# mainboard_rs485_v1_0.net
KiCad netlist of a schematic drawn in Altium Designer
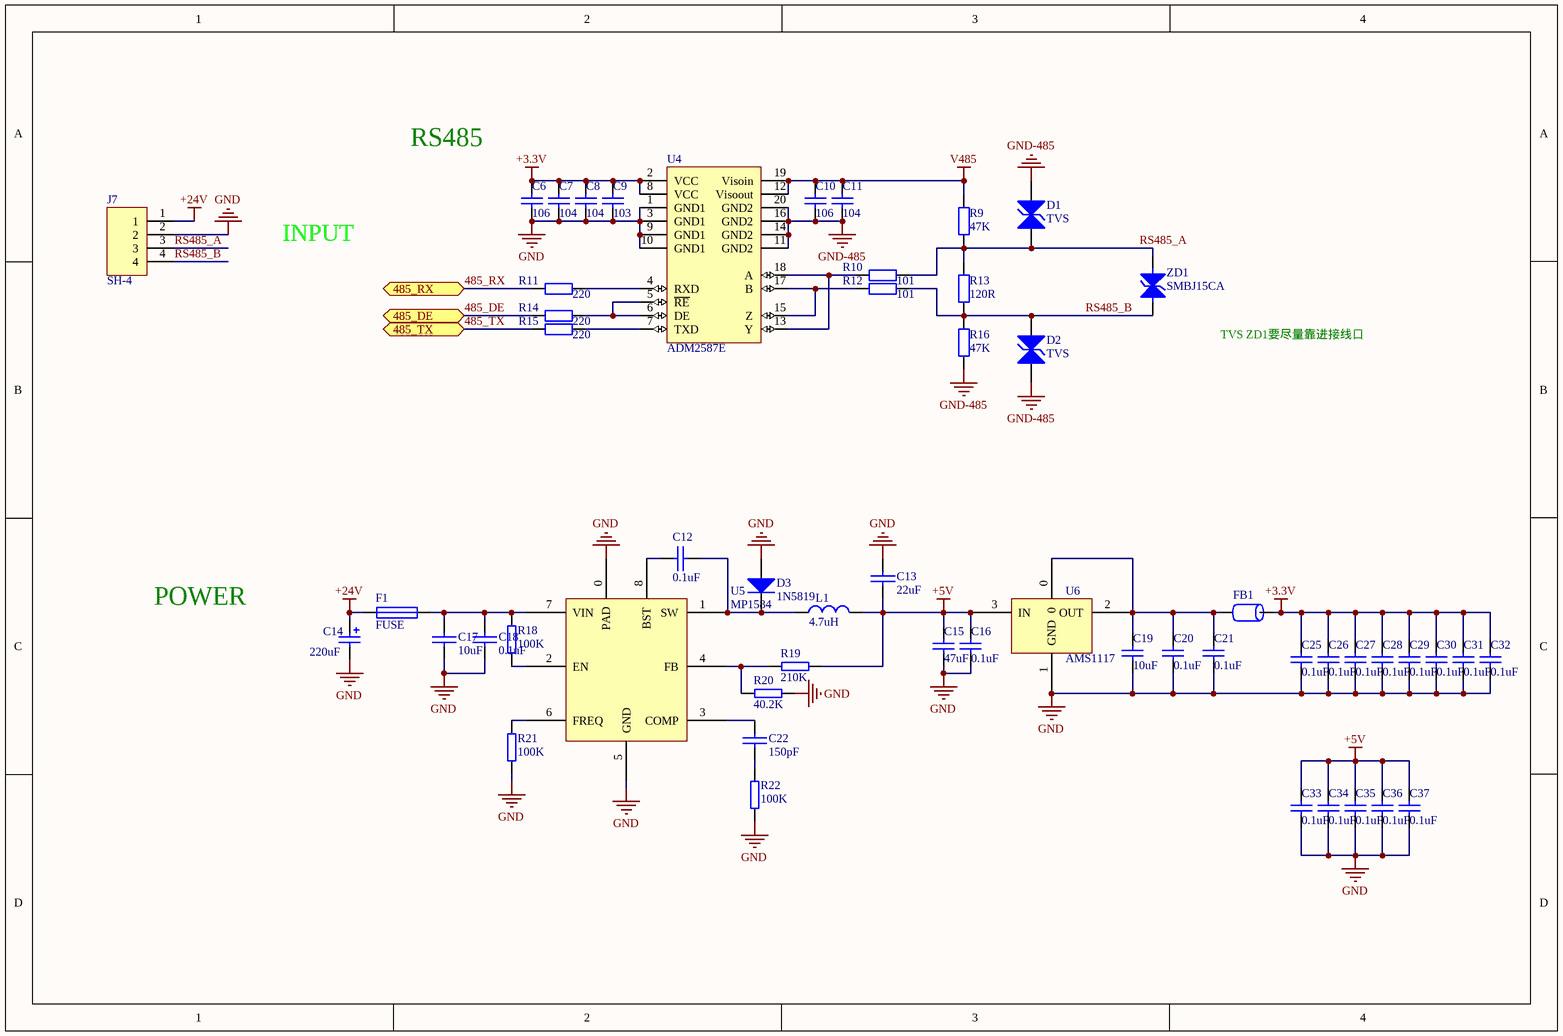
[diagram p0: mainboard_rs485.v1.0.SchDoc]

(export (version "E")
  (design (tool "Eeschema 10.0.6"))
  (components
    (comp (ref "C6")
      (value "106")
      (footprint "0805")
      (description "Capacitor")
      (fields (field (name "PUBLISHER") "Altium Limited"))
      (libsource (lib "TIAN's Schlib") (part "Cap"))
    )
    (comp (ref "C7")
      (value "104")
      (footprint "0805")
      (description "Capacitor")
      (fields (field (name "PUBLISHER") "Altium Limited"))
      (libsource (lib "TIAN's Schlib") (part "Cap"))
    )
    (comp (ref "C8")
      (value "104")
      (footprint "0805")
      (description "Capacitor")
      (fields (field (name "PUBLISHER") "Altium Limited"))
      (libsource (lib "TIAN's Schlib") (part "Cap"))
    )
    (comp (ref "C9")
      (value "103")
      (footprint "0805")
      (description "Capacitor")
      (fields (field (name "PUBLISHER") "Altium Limited"))
      (libsource (lib "TIAN's Schlib") (part "Cap"))
    )
    (comp (ref "C10")
      (value "106")
      (footprint "0805")
      (description "Capacitor")
      (fields (field (name "PUBLISHER") "Altium Limited"))
      (libsource (lib "TIAN's Schlib") (part "Cap"))
    )
    (comp (ref "C11")
      (value "104")
      (footprint "0805")
      (description "Capacitor")
      (fields (field (name "PUBLISHER") "Altium Limited"))
      (libsource (lib "TIAN's Schlib") (part "Cap"))
    )
    (comp (ref "C12")
      (value "0.1uF")
      (footprint "0805")
      (description "电容")
      (libsource (lib "Component") (part "CAP"))
    )
    (comp (ref "C13")
      (value "22uF")
      (footprint "0805")
      (description "电容")
      (libsource (lib "Component") (part "CAP"))
    )
    (comp (ref "C14")
      (value "220uF")
      (footprint "CAP-5mm")
      (description "电解电容")
      (libsource (lib "Component") (part "Cap Pol1"))
    )
    (comp (ref "C15") (value "47uF") (footprint "1812") (libsource (lib "Componet") (part "Cap0805")))
    (comp (ref "C16") (value "0.1uF") (footprint "0805") (libsource (lib "Componet") (part "Cap0805")))
    (comp (ref "C17")
      (value "10uF")
      (footprint "0805")
      (description "电容")
      (libsource (lib "Component") (part "CAP"))
    )
    (comp (ref "C18")
      (value "0.1uF")
      (footprint "0805")
      (description "电容")
      (libsource (lib "Component") (part "CAP"))
    )
    (comp (ref "C19") (value "10uF") (footprint "0805") (libsource (lib "Componet") (part "Cap0805")))
    (comp (ref "C20") (value "0.1uF") (footprint "0805") (libsource (lib "Componet") (part "Cap0805")))
    (comp (ref "C21") (value "0.1uF") (footprint "0805") (libsource (lib "Componet") (part "Cap0805")))
    (comp (ref "C22")
      (value "150pF")
      (footprint "0805")
      (description "电容")
      (libsource (lib "Component") (part "CAP"))
    )
    (comp (ref "C25") (value "0.1uF") (footprint "0805") (libsource (lib "Componet") (part "Cap0805")))
    (comp (ref "C26") (value "0.1uF") (footprint "0805") (libsource (lib "Componet") (part "Cap0805")))
    (comp (ref "C27") (value "0.1uF") (footprint "0805") (libsource (lib "Componet") (part "Cap0805")))
    (comp (ref "C28") (value "0.1uF") (footprint "0805") (libsource (lib "Componet") (part "Cap0805")))
    (comp (ref "C29") (value "0.1uF") (footprint "0805") (libsource (lib "Componet") (part "Cap0805")))
    (comp (ref "C30") (value "0.1uF") (footprint "0805") (libsource (lib "Componet") (part "Cap0805")))
    (comp (ref "C31") (value "0.1uF") (footprint "0805") (libsource (lib "Componet") (part "Cap0805")))
    (comp (ref "C32") (value "0.1uF") (footprint "0805") (libsource (lib "Componet") (part "Cap0805")))
    (comp (ref "C33") (value "0.1uF") (footprint "0805") (libsource (lib "Componet") (part "Cap0805")))
    (comp (ref "C34") (value "0.1uF") (footprint "0805") (libsource (lib "Componet") (part "Cap0805")))
    (comp (ref "C35") (value "0.1uF") (footprint "0805") (libsource (lib "Componet") (part "Cap0805")))
    (comp (ref "C36") (value "0.1uF") (footprint "0805") (libsource (lib "Componet") (part "Cap0805")))
    (comp (ref "C37") (value "0.1uF") (footprint "0805") (libsource (lib "Componet") (part "Cap0805")))
    (comp (ref "D1")
      (value "TVS")
      (footprint "SMBJ_DO-214")
      (fields (field (name "PUBLISHER") "Altium Limited"))
      (libsource (lib "TIAN's Schlib") (part "TVS"))
    )
    (comp (ref "D2")
      (value "TVS")
      (footprint "SMBJ_DO-214")
      (fields (field (name "PUBLISHER") "Altium Limited"))
      (libsource (lib "TIAN's Schlib") (part "TVS"))
    )
    (comp (ref "D3")
      (value "1N5819")
      (footprint "Diode_TP2")
      (description "二极管")
      (fields (field (name "PUBLISHER") "Altium Limited"))
      (libsource (lib "Component") (part "Diode"))
    )
    (comp (ref "F1")
      (value "FUSE")
      (footprint "1206")
      (description "保险丝")
      (libsource (lib "Component") (part "FUSE"))
    )
    (comp (ref "FB1") (value "FERRITE") (footprint "0805") (libsource (lib "Connector") (part "FERRITE")))
    (comp (ref "J7") (value "SH-4") (footprint "J5.08_4(NoEar)") (libsource (lib "Connector") (part "SH-4")))
    (comp (ref "L1")
      (value "4.7uH")
      (footprint "Inductance6*6")
      (description "电感")
      (libsource (lib "Component") (part "Inductor"))
    )
    (comp (ref "R9")
      (value "47K")
      (footprint "0805")
      (description "Resistor")
      (fields (field (name "PUBLISHER") "Altium Limited"))
      (libsource (lib "TIAN's Schlib") (part "Res2"))
    )
    (comp (ref "R10")
      (value "101")
      (footprint "0805")
      (description "Resistor")
      (fields (field (name "PUBLISHER") "Altium Limited"))
      (libsource (lib "") (part "Res2_1"))
    )
    (comp (ref "R11")
      (value "220")
      (footprint "0805")
      (description "Resistor")
      (fields (field (name "PUBLISHER") "Altium Limited"))
      (libsource (lib "TIAN's Schlib") (part "Res2"))
    )
    (comp (ref "R12")
      (value "101")
      (footprint "0805")
      (description "Resistor")
      (fields (field (name "PUBLISHER") "Altium Limited"))
      (libsource (lib "") (part "Res2_1"))
    )
    (comp (ref "R13")
      (value "120R")
      (footprint "0805")
      (description "Resistor")
      (fields (field (name "PUBLISHER") "Altium Limited"))
      (libsource (lib "TIAN's Schlib") (part "Res2"))
    )
    (comp (ref "R14")
      (value "220")
      (footprint "0805")
      (description "Resistor")
      (fields (field (name "PUBLISHER") "Altium Limited"))
      (libsource (lib "TIAN's Schlib") (part "Res2"))
    )
    (comp (ref "R15")
      (value "220")
      (footprint "0805")
      (description "Resistor")
      (fields (field (name "PUBLISHER") "Altium Limited"))
      (libsource (lib "TIAN's Schlib") (part "Res2"))
    )
    (comp (ref "R16")
      (value "47K")
      (footprint "0805")
      (description "Resistor")
      (fields (field (name "PUBLISHER") "Altium Limited"))
      (libsource (lib "TIAN's Schlib") (part "Res2"))
    )
    (comp (ref "R18")
      (value "100K")
      (footprint "0805")
      (description "电阻")
      (libsource (lib "Component") (part "RES"))
    )
    (comp (ref "R19")
      (value "210K")
      (footprint "0805")
      (description "电阻")
      (libsource (lib "Component") (part "RES"))
    )
    (comp (ref "R20")
      (value "40.2K")
      (footprint "0805")
      (description "电阻")
      (libsource (lib "Component") (part "RES"))
    )
    (comp (ref "R21")
      (value "100K")
      (footprint "0805")
      (description "电阻")
      (libsource (lib "Component") (part "RES"))
    )
    (comp (ref "R22")
      (value "100K")
      (footprint "0805")
      (description "电阻")
      (libsource (lib "Component") (part "RES"))
    )
    (comp (ref "U4")
      (value "ADM2587E")
      (footprint "SOIC_W_20")
      (description "isolated DC-DC RS485")
      (libsource (lib "TIAN's Schlib") (part "ADM2587E"))
    )
    (comp (ref "U5") (value "MP1584") (footprint "MP1584") (libsource (lib "Chip") (part "MP1584")))
    (comp (ref "U6") (value "AMS1117") (footprint "TO-223") (libsource (lib "Chip") (part "AMS1117")))
    (comp (ref "ZD1")
      (value "SMBJ15CA")
      (footprint "DO-214AA/SMB")
      (description "瞬态抑制二极管")
      (libsource (lib "ALARM") (part "TVS"))
    )
  )
  (nets
    (net (code "1") (name "+3.3V") (class "Default")
      (node (ref "C25") (pin "2") (pinfunction "2_2") (pintype "passive"))
      (node (ref "C26") (pin "2") (pinfunction "2_2") (pintype "passive"))
      (node (ref "C27") (pin "2") (pinfunction "2_2") (pintype "passive"))
      (node (ref "C28") (pin "2") (pinfunction "2_2") (pintype "passive"))
      (node (ref "C29") (pin "2") (pinfunction "2_2") (pintype "passive"))
      (node (ref "C30") (pin "2") (pinfunction "2_2") (pintype "passive"))
      (node (ref "C31") (pin "2") (pinfunction "2_2") (pintype "passive"))
      (node (ref "C32") (pin "2") (pinfunction "2_2") (pintype "passive"))
      (node (ref "C6") (pin "2") (pinfunction "2_2") (pintype "passive"))
      (node (ref "C7") (pin "2") (pinfunction "2_2") (pintype "passive"))
      (node (ref "C8") (pin "2") (pinfunction "2_2") (pintype "passive"))
      (node (ref "C9") (pin "2") (pinfunction "2_2") (pintype "passive"))
      (node (ref "FB1") (pin "2") (pinfunction "2_2") (pintype "passive"))
      (node (ref "U4") (pin "2") (pinfunction "VCC_2") (pintype "passive"))
      (node (ref "U4") (pin "8") (pinfunction "VCC_8") (pintype "passive"))
    )
    (net (code "2") (name "+5V") (class "Default")
      (node (ref "C13") (pin "2") (pinfunction "2_2") (pintype "passive"))
      (node (ref "C15") (pin "2") (pinfunction "2_2") (pintype "passive"))
      (node (ref "C16") (pin "2") (pinfunction "2_2") (pintype "passive"))
      (node (ref "C33") (pin "2") (pinfunction "2_2") (pintype "passive"))
      (node (ref "C34") (pin "2") (pinfunction "2_2") (pintype "passive"))
      (node (ref "C35") (pin "2") (pinfunction "2_2") (pintype "passive"))
      (node (ref "C36") (pin "2") (pinfunction "2_2") (pintype "passive"))
      (node (ref "C37") (pin "2") (pinfunction "2_2") (pintype "passive"))
      (node (ref "L1") (pin "2") (pinfunction "2_2") (pintype "passive"))
      (node (ref "R19") (pin "1") (pinfunction "1_1") (pintype "passive"))
      (node (ref "U6") (pin "3") (pinfunction "IN_3") (pintype "passive"))
    )
    (net (code "3") (name "+24V") (class "Default")
      (node (ref "C14") (pin "1") (pinfunction "1_1") (pintype "passive"))
      (node (ref "F1") (pin "1") (pinfunction "1_1") (pintype "passive"))
      (node (ref "J7") (pin "1") (pinfunction "1_1") (pintype "passive"))
    )
    (net (code "4") (name "/485_DE") (class "Default")
      (node (ref "R14") (pin "1") (pinfunction "1_1") (pintype "passive"))
    )
    (net (code "5") (name "/485_RX") (class "Default")
      (node (ref "R11") (pin "1") (pinfunction "1_1") (pintype "passive"))
    )
    (net (code "6") (name "/485_TX") (class "Default")
      (node (ref "R15") (pin "1") (pinfunction "1_1") (pintype "passive"))
    )
    (net (code "7") (name "/RS485_A") (class "Default")
      (node (ref "D1") (pin "2") (pinfunction "K_2") (pintype "passive"))
      (node (ref "J7") (pin "3") (pinfunction "3_3") (pintype "passive"))
      (node (ref "R10") (pin "2") (pinfunction "2_2") (pintype "passive"))
      (node (ref "R13") (pin "2") (pinfunction "2_2") (pintype "passive"))
      (node (ref "R9") (pin "1") (pinfunction "1_1") (pintype "passive"))
      (node (ref "ZD1") (pin "1") (pinfunction "1_1") (pintype "passive"))
    )
    (net (code "8") (name "/RS485_B") (class "Default")
      (node (ref "D2") (pin "2") (pinfunction "K_2") (pintype "passive"))
      (node (ref "J7") (pin "4") (pinfunction "4_4") (pintype "passive"))
      (node (ref "R12") (pin "2") (pinfunction "2_2") (pintype "passive"))
      (node (ref "R13") (pin "1") (pinfunction "1_1") (pintype "passive"))
      (node (ref "R16") (pin "2") (pinfunction "2_2") (pintype "passive"))
      (node (ref "ZD1") (pin "2") (pinfunction "2_2") (pintype "passive"))
    )
    (net (code "9") (name "GND") (class "Default")
      (node (ref "C13") (pin "1") (pinfunction "1_1") (pintype "passive"))
      (node (ref "C14") (pin "2") (pinfunction "2_2") (pintype "passive"))
      (node (ref "C15") (pin "1") (pinfunction "1_1") (pintype "passive"))
      (node (ref "C16") (pin "1") (pinfunction "1_1") (pintype "passive"))
      (node (ref "C17") (pin "2") (pinfunction "2_2") (pintype "passive"))
      (node (ref "C18") (pin "2") (pinfunction "2_2") (pintype "passive"))
      (node (ref "C19") (pin "1") (pinfunction "1_1") (pintype "passive"))
      (node (ref "C20") (pin "1") (pinfunction "1_1") (pintype "passive"))
      (node (ref "C21") (pin "1") (pinfunction "1_1") (pintype "passive"))
      (node (ref "C25") (pin "1") (pinfunction "1_1") (pintype "passive"))
      (node (ref "C26") (pin "1") (pinfunction "1_1") (pintype "passive"))
      (node (ref "C27") (pin "1") (pinfunction "1_1") (pintype "passive"))
      (node (ref "C28") (pin "1") (pinfunction "1_1") (pintype "passive"))
      (node (ref "C29") (pin "1") (pinfunction "1_1") (pintype "passive"))
      (node (ref "C30") (pin "1") (pinfunction "1_1") (pintype "passive"))
      (node (ref "C31") (pin "1") (pinfunction "1_1") (pintype "passive"))
      (node (ref "C32") (pin "1") (pinfunction "1_1") (pintype "passive"))
      (node (ref "C33") (pin "1") (pinfunction "1_1") (pintype "passive"))
      (node (ref "C34") (pin "1") (pinfunction "1_1") (pintype "passive"))
      (node (ref "C35") (pin "1") (pinfunction "1_1") (pintype "passive"))
      (node (ref "C36") (pin "1") (pinfunction "1_1") (pintype "passive"))
      (node (ref "C37") (pin "1") (pinfunction "1_1") (pintype "passive"))
      (node (ref "C6") (pin "1") (pinfunction "1_1") (pintype "passive"))
      (node (ref "C7") (pin "1") (pinfunction "1_1") (pintype "passive"))
      (node (ref "C8") (pin "1") (pinfunction "1_1") (pintype "passive"))
      (node (ref "C9") (pin "1") (pinfunction "1_1") (pintype "passive"))
      (node (ref "D3") (pin "1") (pinfunction "A_1") (pintype "passive"))
      (node (ref "J7") (pin "2") (pinfunction "2_2") (pintype "passive"))
      (node (ref "R20") (pin "1") (pinfunction "1_1") (pintype "passive"))
      (node (ref "R21") (pin "1") (pinfunction "1_1") (pintype "passive"))
      (node (ref "R22") (pin "1") (pinfunction "1_1") (pintype "passive"))
      (node (ref "U4") (pin "1") (pinfunction "GND1_1") (pintype "passive"))
      (node (ref "U4") (pin "10") (pinfunction "GND1_10") (pintype "passive"))
      (node (ref "U4") (pin "3") (pinfunction "GND1_3") (pintype "passive"))
      (node (ref "U4") (pin "9") (pinfunction "GND1_9") (pintype "passive"))
      (node (ref "U5") (pin "0") (pinfunction "PAD_0") (pintype "passive"))
      (node (ref "U5") (pin "5") (pinfunction "GND_5") (pintype "passive"))
      (node (ref "U6") (pin "1") (pinfunction "GND_1") (pintype "passive"))
    )
    (net (code "10") (name "GND-485") (class "Default")
      (node (ref "C10") (pin "1") (pinfunction "1_1") (pintype "passive"))
      (node (ref "C11") (pin "1") (pinfunction "1_1") (pintype "passive"))
      (node (ref "D1") (pin "1") (pinfunction "A_1") (pintype "passive"))
      (node (ref "D2") (pin "1") (pinfunction "A_1") (pintype "passive"))
      (node (ref "R16") (pin "1") (pinfunction "1_1") (pintype "passive"))
      (node (ref "U4") (pin "11") (pinfunction "GND2_11") (pintype "passive"))
      (node (ref "U4") (pin "14") (pinfunction "GND2_14") (pintype "passive"))
      (node (ref "U4") (pin "16") (pinfunction "GND2_16") (pintype "passive"))
      (node (ref "U4") (pin "20") (pinfunction "GND2_20") (pintype "passive"))
    )
    (net (code "11") (name "Net-(C22-Pad2)") (class "Default")
      (node (ref "C22") (pin "2") (pinfunction "2_2") (pintype "passive"))
      (node (ref "R22") (pin "2") (pinfunction "2_2") (pintype "passive"))
    )
    (net (code "12") (name "Net-(D3-K)") (class "Default")
      (node (ref "C12") (pin "2") (pinfunction "2_2") (pintype "passive"))
      (node (ref "D3") (pin "2") (pinfunction "K_2") (pintype "passive"))
      (node (ref "L1") (pin "1") (pinfunction "1_1") (pintype "passive"))
      (node (ref "U5") (pin "1") (pinfunction "SW_1") (pintype "passive"))
    )
    (net (code "13") (name "Net-(U4-A)") (class "Default")
      (node (ref "R10") (pin "1") (pinfunction "1_1") (pintype "passive"))
      (node (ref "U4") (pin "13") (pinfunction "Y_13") (pintype "bidirectional"))
      (node (ref "U4") (pin "18") (pinfunction "A_18") (pintype "bidirectional"))
    )
    (net (code "14") (name "Net-(U4-B)") (class "Default")
      (node (ref "R12") (pin "1") (pinfunction "1_1") (pintype "passive"))
      (node (ref "U4") (pin "15") (pinfunction "Z_15") (pintype "bidirectional"))
      (node (ref "U4") (pin "17") (pinfunction "B_17") (pintype "bidirectional"))
    )
    (net (code "15") (name "Net-(U4-DE)") (class "Default")
      (node (ref "R14") (pin "2") (pinfunction "2_2") (pintype "passive"))
      (node (ref "U4") (pin "5") (pinfunction "~{RE}_5") (pintype "bidirectional"))
      (node (ref "U4") (pin "6") (pinfunction "DE_6") (pintype "bidirectional"))
    )
    (net (code "16") (name "Net-(U4-RXD)") (class "Default")
      (node (ref "R11") (pin "2") (pinfunction "2_2") (pintype "passive"))
      (node (ref "U4") (pin "4") (pinfunction "RXD_4") (pintype "bidirectional"))
    )
    (net (code "17") (name "Net-(U4-TXD)") (class "Default")
      (node (ref "R15") (pin "2") (pinfunction "2_2") (pintype "passive"))
      (node (ref "U4") (pin "7") (pinfunction "TXD_7") (pintype "bidirectional"))
    )
    (net (code "18") (name "Net-(U5-BST)") (class "Default")
      (node (ref "C12") (pin "1") (pinfunction "1_1") (pintype "passive"))
      (node (ref "U5") (pin "8") (pinfunction "BST_8") (pintype "passive"))
    )
    (net (code "19") (name "Net-(U5-COMP)") (class "Default")
      (node (ref "C22") (pin "1") (pinfunction "1_1") (pintype "passive"))
      (node (ref "U5") (pin "3") (pinfunction "COMP_3") (pintype "passive"))
    )
    (net (code "20") (name "Net-(U5-EN)") (class "Default")
      (node (ref "R18") (pin "1") (pinfunction "1_1") (pintype "passive"))
      (node (ref "U5") (pin "2") (pinfunction "EN_2") (pintype "passive"))
    )
    (net (code "21") (name "Net-(U5-FB)") (class "Default")
      (node (ref "R19") (pin "2") (pinfunction "2_2") (pintype "passive"))
      (node (ref "R20") (pin "2") (pinfunction "2_2") (pintype "passive"))
      (node (ref "U5") (pin "4") (pinfunction "FB_4") (pintype "passive"))
    )
    (net (code "22") (name "Net-(U5-FREQ)") (class "Default")
      (node (ref "R21") (pin "2") (pinfunction "2_2") (pintype "passive"))
      (node (ref "U5") (pin "6") (pinfunction "FREQ_6") (pintype "passive"))
    )
    (net (code "23") (name "Net-(U5-VIN)") (class "Default")
      (node (ref "C17") (pin "1") (pinfunction "1_1") (pintype "passive"))
      (node (ref "C18") (pin "1") (pinfunction "1_1") (pintype "passive"))
      (node (ref "F1") (pin "2") (pinfunction "2_2") (pintype "passive"))
      (node (ref "R18") (pin "2") (pinfunction "2_2") (pintype "passive"))
      (node (ref "U5") (pin "7") (pinfunction "VIN_7") (pintype "passive"))
    )
    (net (code "24") (name "Net-(U6-OUT)") (class "Default")
      (node (ref "C19") (pin "2") (pinfunction "2_2") (pintype "passive"))
      (node (ref "C20") (pin "2") (pinfunction "2_2") (pintype "passive"))
      (node (ref "C21") (pin "2") (pinfunction "2_2") (pintype "passive"))
      (node (ref "FB1") (pin "1") (pinfunction "1_1") (pintype "passive"))
      (node (ref "U6") (pin "0") (pinfunction "0_0") (pintype "passive"))
      (node (ref "U6") (pin "2") (pinfunction "OUT_2") (pintype "passive"))
    )
    (net (code "25") (name "V485") (class "Default")
      (node (ref "C10") (pin "2") (pinfunction "2_2") (pintype "passive"))
      (node (ref "C11") (pin "2") (pinfunction "2_2") (pintype "passive"))
      (node (ref "R9") (pin "2") (pinfunction "2_2") (pintype "passive"))
      (node (ref "U4") (pin "12") (pinfunction "Visoout_12") (pintype "passive"))
      (node (ref "U4") (pin "19") (pinfunction "Visoin_19") (pintype "passive"))
    )
  )
)
